# 3V_ADC_SUPPLY.net
KiCad netlist of a schematic drawn in Altium Designer
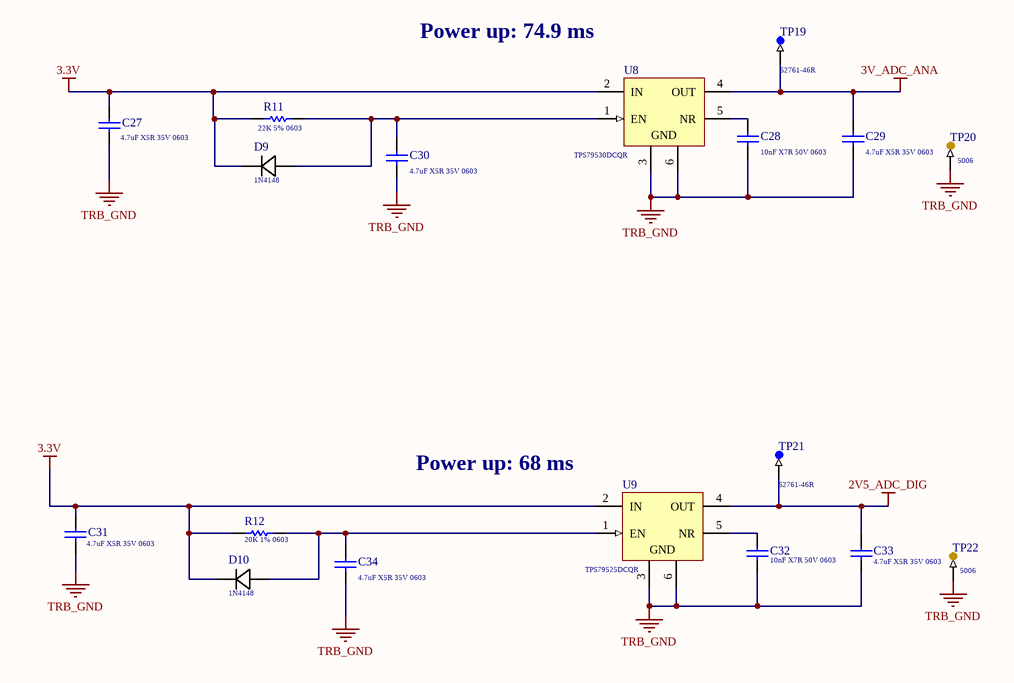
[diagram p0: 3V_ADC_SUPPLY.SchDoc]

(export (version "E")
  (design (tool "Eeschema 10.0.6"))
  (components
    (comp (ref "C27")
      (value "Cap_Murata_ZRB18AR6YA475ME05L_4.7uF")
      (footprint "Cap_Murata_ZRB18AR6YA475ME05L_4.7uF")
      (description "CAP CER 4.7uF 35V X5R 0603")
      (fields (field (name "CAPACITANCE") "4.7uF X5R 35V 0603"))
      (libsource (lib "Cap_Murata_ZRB18AR6YA475ME05L_4.7uF") (part "Cap_Murata_ZRB18AR6YA475ME05L_4.7uF"))
    )
    (comp (ref "C28")
      (value "Cap_Kemet_C0603C103J5RACTU_eec")
      (footprint "Kemet_C0603_0")
      (description "CAP CER 10nF 50V X7R 0603")
      (fields
        (field (name "PART NUMBER") "C0603C103J5RACTU")
        (field (name "MANUFACTURER") "Kemet")
        (field (name "CAPACITANCE") "10nF X7R 50V 0603")
      )
      (libsource (lib "Cap_Kemet_C0603C103J5RACTU_10nF") (part "Cap_Kemet_C0603C103J5RACTU_eec"))
    )
    (comp (ref "C29")
      (value "Cap_Murata_ZRB18AR6YA475ME05L_4.7uF")
      (footprint "Cap_Murata_ZRB18AR6YA475ME05L_4.7uF")
      (description "CAP CER 4.7uF 35V X5R 0603")
      (fields (field (name "CAPACITANCE") "4.7uF X5R 35V 0603"))
      (libsource (lib "Cap_Murata_ZRB18AR6YA475ME05L_4.7uF") (part "Cap_Murata_ZRB18AR6YA475ME05L_4.7uF"))
    )
    (comp (ref "C30")
      (value "Cap_Murata_ZRB18AR6YA475ME05L_4.7uF")
      (footprint "Cap_Murata_ZRB18AR6YA475ME05L_4.7uF")
      (description "CAP CER 4.7uF 35V X5R 0603")
      (fields (field (name "CAPACITANCE") "4.7uF X5R 35V 0603"))
      (libsource (lib "Cap_Murata_ZRB18AR6YA475ME05L_4.7uF") (part "Cap_Murata_ZRB18AR6YA475ME05L_4.7uF"))
    )
    (comp (ref "C31")
      (value "Cap_Murata_ZRB18AR6YA475ME05L_4.7uF")
      (footprint "Cap_Murata_ZRB18AR6YA475ME05L_4.7uF")
      (description "CAP CER 4.7uF 35V X5R 0603")
      (fields (field (name "CAPACITANCE") "4.7uF X5R 35V 0603"))
      (libsource (lib "Cap_Murata_ZRB18AR6YA475ME05L_4.7uF") (part "Cap_Murata_ZRB18AR6YA475ME05L_4.7uF"))
    )
    (comp (ref "C32")
      (value "Cap_Kemet_C0603C103J5RACTU_eec")
      (footprint "Kemet_C0603_0")
      (description "CAP CER 10nF 50V X7R 0603")
      (fields
        (field (name "PART NUMBER") "C0603C103J5RACTU")
        (field (name "MANUFACTURER") "Kemet")
        (field (name "CAPACITANCE") "10nF X7R 50V 0603")
      )
      (libsource (lib "Cap_Kemet_C0603C103J5RACTU_10nF") (part "Cap_Kemet_C0603C103J5RACTU_eec"))
    )
    (comp (ref "C33")
      (value "Cap_Murata_ZRB18AR6YA475ME05L_4.7uF")
      (footprint "Cap_Murata_ZRB18AR6YA475ME05L_4.7uF")
      (description "CAP CER 4.7uF 35V X5R 0603")
      (fields (field (name "CAPACITANCE") "4.7uF X5R 35V 0603"))
      (libsource (lib "Cap_Murata_ZRB18AR6YA475ME05L_4.7uF") (part "Cap_Murata_ZRB18AR6YA475ME05L_4.7uF"))
    )
    (comp (ref "C34")
      (value "Cap_Murata_ZRB18AR6YA475ME05L_4.7uF")
      (footprint "Cap_Murata_ZRB18AR6YA475ME05L_4.7uF")
      (description "CAP CER 4.7uF 35V X5R 0603")
      (fields (field (name "CAPACITANCE") "4.7uF X5R 35V 0603"))
      (libsource (lib "Cap_Murata_ZRB18AR6YA475ME05L_4.7uF") (part "Cap_Murata_ZRB18AR6YA475ME05L_4.7uF"))
    )
    (comp (ref "D9")
      (value "Diode_ON_Semiconductor_1N4148WT_300mA")
      (footprint "Diode_ON_Semiconductor_1N4148WT_300mA")
      (description "Diodes - General Purpose, Power, Switching SINGLE JUNC. 75V 4.0NS COMP")
      (fields (field (name "SERIES") "1N4148"))
      (libsource (lib "Diode_ON_Semiconductor_1N4148WT_300mA") (part "Diode_ON_Semiconductor_1N4148WT_300mA"))
    )
    (comp (ref "D10")
      (value "Diode_ON_Semiconductor_1N4148WT_300mA")
      (footprint "Diode_ON_Semiconductor_1N4148WT_300mA")
      (description "Diodes - General Purpose, Power, Switching SINGLE JUNC. 75V 4.0NS COMP")
      (fields (field (name "SERIES") "1N4148"))
      (libsource (lib "Diode_ON_Semiconductor_1N4148WT_300mA") (part "Diode_ON_Semiconductor_1N4148WT_300mA"))
    )
    (comp (ref "R11")
      (value "22K 5% 0603")
      (footprint "RESC0603(1608)_L")
      (description "22K 0.1W 5% 0603 (1608 Metric)  SMD")
      (fields (field (name "POWER") "0.1 W") (field (name "TOLERANCE") "5 %"))
      (libsource (lib "Altium Content Vault") (part "RES"))
    )
    (comp (ref "R12")
      (value "20K 1% 0603")
      (footprint "RESC0603(1608)_L")
      (description "20K 0.1W 1% 0603 (1608 Metric)  SMD")
      (fields (field (name "TOLERANCE") "1 %") (field (name "POWER") "0.1 W"))
      (libsource (lib "Altium Content Vault") (part "RES"))
    )
    (comp (ref "TP19")
      (value "TP_Harwin_S2761_46R")
      (footprint "TP_Harwin_S2761_46R")
      (description "Circuit Board Hardware - PCB SMT Mini Test Terminal, Reel")
      (fields (field (name "SERIES") "S2761-46R"))
      (libsource (lib "TP_Harwin_S2761_46R") (part "TP_Harwin_S2761_46R"))
    )
    (comp (ref "TP20")
      (value "TP_Keystone_Electronics_5006")
      (footprint "TP_Keystone_Electronics_5006")
      (description "Circuit Board Hardware - PCB TEST POINT BLK .063")
      (fields (field (name "SERIES") "5006"))
      (libsource (lib "TP_Keystone_Electronics_5006") (part "TP_Keystone_Electronics_5006"))
    )
    (comp (ref "TP21")
      (value "TP_Harwin_S2761_46R")
      (footprint "TP_Harwin_S2761_46R")
      (description "Circuit Board Hardware - PCB SMT Mini Test Terminal, Reel")
      (fields (field (name "SERIES") "S2761-46R"))
      (libsource (lib "TP_Harwin_S2761_46R") (part "TP_Harwin_S2761_46R"))
    )
    (comp (ref "TP22")
      (value "TP_Keystone_Electronics_5006")
      (footprint "TP_Keystone_Electronics_5006")
      (description "Circuit Board Hardware - PCB TEST POINT BLK .063")
      (fields (field (name "SERIES") "5006"))
      (libsource (lib "TP_Keystone_Electronics_5006") (part "TP_Keystone_Electronics_5006"))
    )
    (comp (ref "U8")
      (value "TPS79530DCQR")
      (footprint "TI-DCQ6_N")
      (fields (field (name "MANUFACTURER") "Texas Instruments"))
      (libsource (lib "IC_Texas_Instruments_TPS79530DCQR") (part "TPS79530DCQR"))
    )
    (comp (ref "U9")
      (value "TPS79525DCQR")
      (footprint "DCQ0006A_N")
      (fields (field (name "MANUFACTURER") "Texas Instruments"))
      (libsource (lib "IC_Texas Instruments_TPS79525DCQR") (part "TPS79525DCQR"))
    )
  )
  (nets
    (net (code "1") (name "2V5_ADC_DIG") (class "Default")
      (node (ref "C33") (pin "2") (pinfunction "2_2") (pintype "passive"))
      (node (ref "TP21") (pin "1") (pinfunction "1_1") (pintype "input"))
      (node (ref "U9") (pin "4") (pinfunction "OUT_4") (pintype "power_in"))
    )
    (net (code "2") (name "3.3V") (class "Default")
      (node (ref "C27") (pin "2") (pinfunction "2_2") (pintype "passive"))
      (node (ref "C31") (pin "2") (pinfunction "2_2") (pintype "passive"))
      (node (ref "D10") (pin "1") (pinfunction "1_1") (pintype "passive"))
      (node (ref "D9") (pin "1") (pinfunction "1_1") (pintype "passive"))
      (node (ref "R11") (pin "1") (pinfunction "1_1") (pintype "passive"))
      (node (ref "R12") (pin "2") (pinfunction "2_2") (pintype "passive"))
      (node (ref "U8") (pin "2") (pinfunction "IN_2") (pintype "power_in"))
      (node (ref "U9") (pin "2") (pinfunction "IN_2") (pintype "power_in"))
    )
    (net (code "3") (name "3V_ADC_ANA") (class "Default")
      (node (ref "C29") (pin "2") (pinfunction "2_2") (pintype "passive"))
      (node (ref "TP19") (pin "1") (pinfunction "1_1") (pintype "input"))
      (node (ref "U8") (pin "4") (pinfunction "OUT_4") (pintype "power_in"))
    )
    (net (code "4") (name "Net-(U8-EN)") (class "Default")
      (node (ref "C30") (pin "2") (pinfunction "2_2") (pintype "passive"))
      (node (ref "D9") (pin "2") (pinfunction "2_2") (pintype "passive"))
      (node (ref "R11") (pin "2") (pinfunction "2_2") (pintype "passive"))
      (node (ref "U8") (pin "1") (pinfunction "EN_1") (pintype "input"))
    )
    (net (code "5") (name "Net-(U8-NR)") (class "Default")
      (node (ref "C28") (pin "1") (pinfunction "1_1") (pintype "passive"))
      (node (ref "U8") (pin "5") (pinfunction "NR_5") (pintype "passive"))
    )
    (net (code "6") (name "Net-(U9-EN)") (class "Default")
      (node (ref "C34") (pin "2") (pinfunction "2_2") (pintype "passive"))
      (node (ref "D10") (pin "2") (pinfunction "2_2") (pintype "passive"))
      (node (ref "R12") (pin "1") (pinfunction "1_1") (pintype "passive"))
      (node (ref "U9") (pin "1") (pinfunction "EN_1") (pintype "input"))
    )
    (net (code "7") (name "Net-(U9-NR)") (class "Default")
      (node (ref "C32") (pin "1") (pinfunction "1_1") (pintype "passive"))
      (node (ref "U9") (pin "5") (pinfunction "NR_5") (pintype "passive"))
    )
    (net (code "8") (name "TRB_GND") (class "Default")
      (node (ref "C27") (pin "1") (pinfunction "1_1") (pintype "passive"))
      (node (ref "C28") (pin "2") (pinfunction "2_2") (pintype "passive"))
      (node (ref "C29") (pin "1") (pinfunction "1_1") (pintype "passive"))
      (node (ref "C30") (pin "1") (pinfunction "1_1") (pintype "passive"))
      (node (ref "C31") (pin "1") (pinfunction "1_1") (pintype "passive"))
      (node (ref "C32") (pin "2") (pinfunction "2_2") (pintype "passive"))
      (node (ref "C33") (pin "1") (pinfunction "1_1") (pintype "passive"))
      (node (ref "C34") (pin "1") (pinfunction "1_1") (pintype "passive"))
      (node (ref "TP20") (pin "1") (pinfunction "1_1") (pintype "input"))
      (node (ref "TP22") (pin "1") (pinfunction "1_1") (pintype "input"))
      (node (ref "U8") (pin "3") (pinfunction "GND_3") (pintype "power_in"))
      (node (ref "U8") (pin "6") (pinfunction "GND_6") (pintype "power_in"))
      (node (ref "U9") (pin "3") (pinfunction "GND_3") (pintype "power_in"))
      (node (ref "U9") (pin "6") (pinfunction "GND_6") (pintype "power_in"))
    )
  )
)
